# 8_-RK3399_SDRAM_Page.net
KiCad netlist of a schematic drawn in Altium Designer
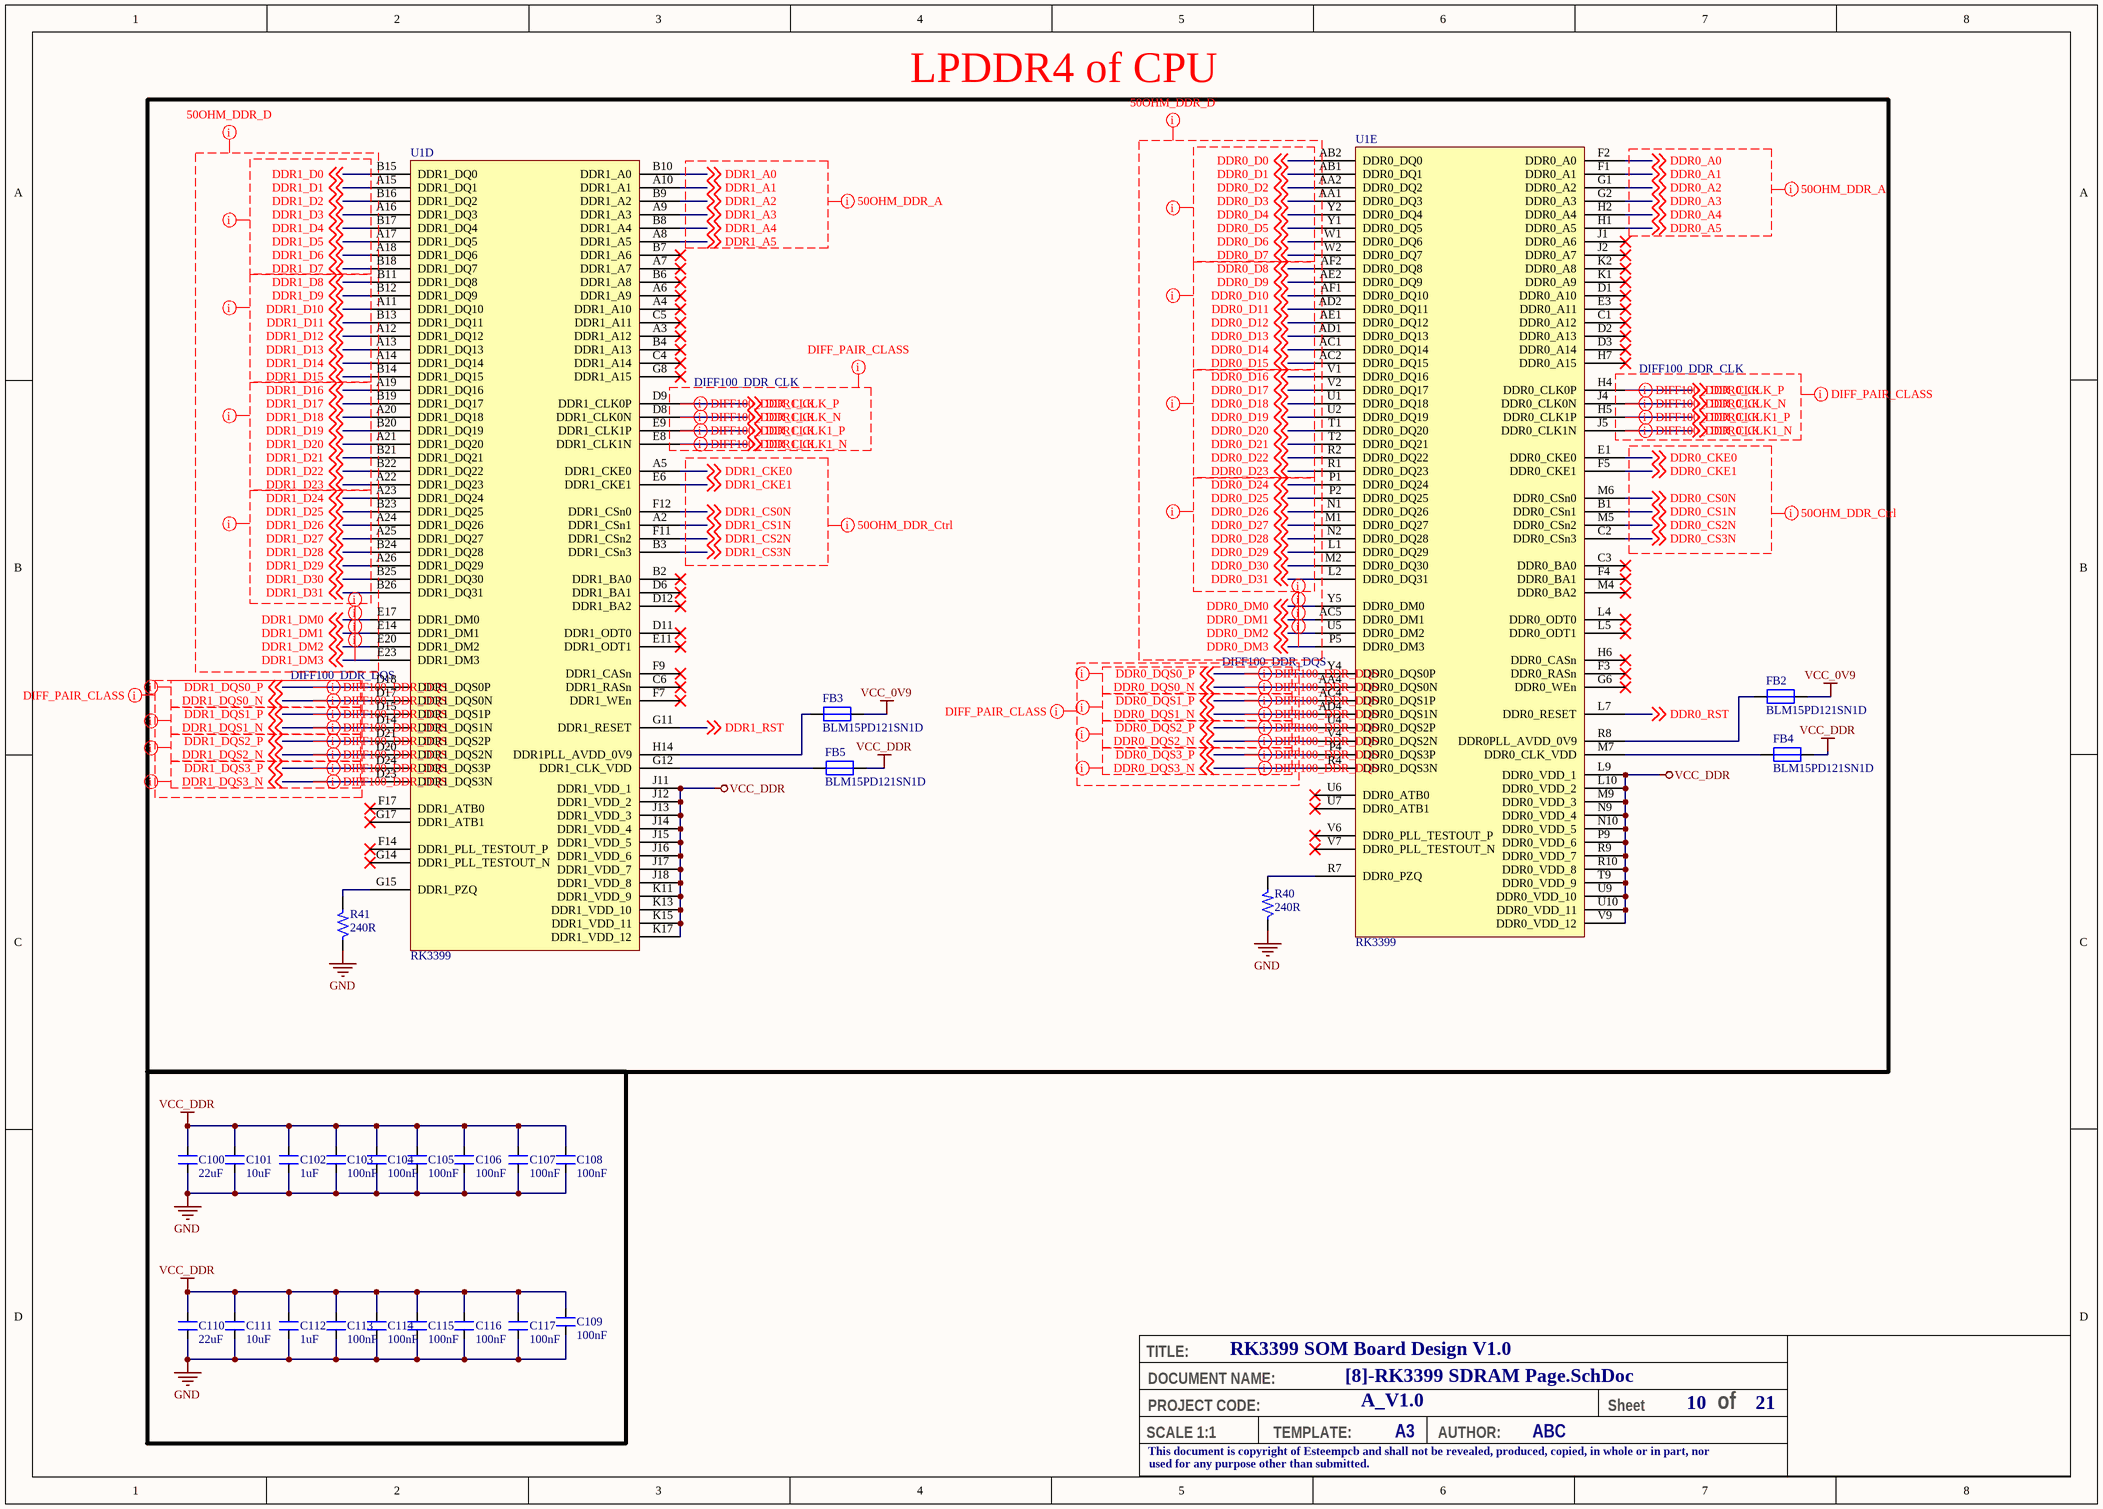
[diagram p0: [8]-RK3399 SDRAM Page.SchDoc]

(export (version "E")
  (design (tool "Eeschema 10.0.6"))
  (components
    (comp (ref "C100")
      (value "22uF")
      (footprint "CAP_0402")
      (description "22µF ±20% 6.3V Ceramic Capacitor X5R 0402 (1005 Metric)")
      (fields
        (field (name "MANUFACTURER") "Murata Electronics")
        (field (name "MANUFACTURER PART NUMBER") "CL05A226MQ5N6J8")
      )
      (libsource (lib "RK3399 _Module_Intlib") (part "CAP_22uF-6.3V-20%-0402"))
    )
    (comp (ref "C101")
      (value "10uF")
      (footprint "CAP_0402")
      (description "10µF ±20% 10V Ceramic Capacitor X5R 0402 (1005 Metric)")
      (fields
        (field (name "MANUFACTURER PART NUMBER") "CL05A106MP5NUNC")
        (field (name "MANUFACTURER") "Samsung Electro-Mechanics")
      )
      (libsource (lib "RK3399 _Module_Schlib") (part "CAP_10uF-10V-20%-0402"))
    )
    (comp (ref "C102")
      (value "1uF")
      (footprint "CAP_0201")
      (description "1µF ±20% 16V Ceramic Capacitor X5R 0201 (0603 Metric)")
      (fields
        (field (name "MANUFACTURER") "Samsung Electro-Mechanics")
        (field (name "MANUFACTURER PART NUMBER") "CL03A105MO3NRNH")
      )
      (libsource (lib "RK3399 _Module_Intlib") (part "CAP_1uF-16V-10%-0201"))
    )
    (comp (ref "C103")
      (value "100nF")
      (footprint "CAP_0201")
      (description "0.1µF ±10% 25V Ceramic Capacitor X5R 0201 (0603 Metric)")
      (fields
        (field (name "MANUFACTURER") "TDK Corporation")
        (field (name "MANUFACTURER PART NUMBER") "C0603X5R1E104K030BB")
      )
      (libsource (lib "RK3399 _Module_Intlib") (part "CAP_100nF-25V-10%-0201"))
    )
    (comp (ref "C104")
      (value "100nF")
      (footprint "CAP_0201")
      (description "0.1µF ±10% 25V Ceramic Capacitor X5R 0201 (0603 Metric)")
      (fields
        (field (name "MANUFACTURER") "TDK Corporation")
        (field (name "MANUFACTURER PART NUMBER") "C0603X5R1E104K030BB")
      )
      (libsource (lib "RK3399 _Module_Intlib") (part "CAP_100nF-25V-10%-0201"))
    )
    (comp (ref "C105")
      (value "100nF")
      (footprint "CAP_0201")
      (description "0.1µF ±10% 25V Ceramic Capacitor X5R 0201 (0603 Metric)")
      (fields
        (field (name "MANUFACTURER") "TDK Corporation")
        (field (name "MANUFACTURER PART NUMBER") "C0603X5R1E104K030BB")
      )
      (libsource (lib "RK3399 _Module_Intlib") (part "CAP_100nF-25V-10%-0201"))
    )
    (comp (ref "C106")
      (value "100nF")
      (footprint "CAP_0201")
      (description "0.1µF ±10% 25V Ceramic Capacitor X5R 0201 (0603 Metric)")
      (fields
        (field (name "MANUFACTURER") "TDK Corporation")
        (field (name "MANUFACTURER PART NUMBER") "C0603X5R1E104K030BB")
      )
      (libsource (lib "RK3399 _Module_Intlib") (part "CAP_100nF-25V-10%-0201"))
    )
    (comp (ref "C107")
      (value "100nF")
      (footprint "CAP_0201")
      (description "0.1µF ±10% 25V Ceramic Capacitor X5R 0201 (0603 Metric)")
      (fields
        (field (name "MANUFACTURER") "TDK Corporation")
        (field (name "MANUFACTURER PART NUMBER") "C0603X5R1E104K030BB")
      )
      (libsource (lib "RK3399 _Module_Intlib") (part "CAP_100nF-25V-10%-0201"))
    )
    (comp (ref "C108")
      (value "100nF")
      (footprint "CAP_0201")
      (description "0.1µF ±10% 25V Ceramic Capacitor X5R 0201 (0603 Metric)")
      (fields
        (field (name "MANUFACTURER") "TDK Corporation")
        (field (name "MANUFACTURER PART NUMBER") "C0603X5R1E104K030BB")
      )
      (libsource (lib "RK3399 _Module_Intlib") (part "CAP_100nF-25V-10%-0201"))
    )
    (comp (ref "C109")
      (value "100nF")
      (footprint "CAP_0201")
      (description "0.1µF ±10% 25V Ceramic Capacitor X5R 0201 (0603 Metric)")
      (fields
        (field (name "MANUFACTURER") "TDK Corporation")
        (field (name "MANUFACTURER PART NUMBER") "C0603X5R1E104K030BB")
      )
      (libsource (lib "RK3399 _Module_Intlib") (part "CAP_100nF-25V-10%-0201"))
    )
    (comp (ref "C110")
      (value "22uF")
      (footprint "CAP_0402")
      (description "22µF ±20% 6.3V Ceramic Capacitor X5R 0402 (1005 Metric)")
      (fields
        (field (name "MANUFACTURER") "Murata Electronics")
        (field (name "MANUFACTURER PART NUMBER") "CL05A226MQ5N6J8")
      )
      (libsource (lib "RK3399 _Module_Intlib") (part "CAP_22uF-6.3V-20%-0402"))
    )
    (comp (ref "C111")
      (value "10uF")
      (footprint "CAP_0402")
      (description "10µF ±20% 10V Ceramic Capacitor X5R 0402 (1005 Metric)")
      (fields
        (field (name "MANUFACTURER PART NUMBER") "CL05A106MP5NUNC")
        (field (name "MANUFACTURER") "Samsung Electro-Mechanics")
      )
      (libsource (lib "RK3399 _Module_Schlib") (part "CAP_10uF-10V-20%-0402"))
    )
    (comp (ref "C112")
      (value "1uF")
      (footprint "CAP_0201")
      (description "1µF ±20% 16V Ceramic Capacitor X5R 0201 (0603 Metric)")
      (fields
        (field (name "MANUFACTURER") "Samsung Electro-Mechanics")
        (field (name "MANUFACTURER PART NUMBER") "CL03A105MO3NRNH")
      )
      (libsource (lib "RK3399 _Module_Intlib") (part "CAP_1uF-16V-10%-0201"))
    )
    (comp (ref "C113")
      (value "100nF")
      (footprint "CAP_0201")
      (description "0.1µF ±10% 25V Ceramic Capacitor X5R 0201 (0603 Metric)")
      (fields
        (field (name "MANUFACTURER") "TDK Corporation")
        (field (name "MANUFACTURER PART NUMBER") "C0603X5R1E104K030BB")
      )
      (libsource (lib "RK3399 _Module_Intlib") (part "CAP_100nF-25V-10%-0201"))
    )
    (comp (ref "C114")
      (value "100nF")
      (footprint "CAP_0201")
      (description "0.1µF ±10% 25V Ceramic Capacitor X5R 0201 (0603 Metric)")
      (fields
        (field (name "MANUFACTURER") "TDK Corporation")
        (field (name "MANUFACTURER PART NUMBER") "C0603X5R1E104K030BB")
      )
      (libsource (lib "RK3399 _Module_Intlib") (part "CAP_100nF-25V-10%-0201"))
    )
    (comp (ref "C115")
      (value "100nF")
      (footprint "CAP_0201")
      (description "0.1µF ±10% 25V Ceramic Capacitor X5R 0201 (0603 Metric)")
      (fields
        (field (name "MANUFACTURER") "TDK Corporation")
        (field (name "MANUFACTURER PART NUMBER") "C0603X5R1E104K030BB")
      )
      (libsource (lib "RK3399 _Module_Intlib") (part "CAP_100nF-25V-10%-0201"))
    )
    (comp (ref "C116")
      (value "100nF")
      (footprint "CAP_0201")
      (description "0.1µF ±10% 25V Ceramic Capacitor X5R 0201 (0603 Metric)")
      (fields
        (field (name "MANUFACTURER") "TDK Corporation")
        (field (name "MANUFACTURER PART NUMBER") "C0603X5R1E104K030BB")
      )
      (libsource (lib "RK3399 _Module_Intlib") (part "CAP_100nF-25V-10%-0201"))
    )
    (comp (ref "C117")
      (value "100nF")
      (footprint "CAP_0201")
      (description "0.1µF ±10% 25V Ceramic Capacitor X5R 0201 (0603 Metric)")
      (fields
        (field (name "MANUFACTURER") "TDK Corporation")
        (field (name "MANUFACTURER PART NUMBER") "C0603X5R1E104K030BB")
      )
      (libsource (lib "RK3399 _Module_Intlib") (part "CAP_100nF-25V-10%-0201"))
    )
    (comp (ref "FB2")
      (value "BLM15PD121SN1D")
      (footprint "RES_0402")
      (description "120 Ohms @ 100MHz 1 Power Line Ferrite Bead 0402 (1005 Metric) 1.3A 90mOhm")
      (fields (field (name "MANUFACTURER") "Murata Electronics"))
      (libsource (lib "RK3399 _Module_Schlib") (part "FB_120R-1.3A-100Mhz-0402"))
    )
    (comp (ref "FB3")
      (value "BLM15PD121SN1D")
      (footprint "RES_0402")
      (description "120 Ohms @ 100MHz 1 Power Line Ferrite Bead 0402 (1005 Metric) 1.3A 90mOhm")
      (fields (field (name "MANUFACTURER") "Murata Electronics"))
      (libsource (lib "RK3399 _Module_Schlib") (part "FB_120R-1.3A-100Mhz-0402"))
    )
    (comp (ref "FB4")
      (value "BLM15PD121SN1D")
      (footprint "RES_0402")
      (description "120 Ohms @ 100MHz 1 Power Line Ferrite Bead 0402 (1005 Metric) 1.3A 90mOhm")
      (fields (field (name "MANUFACTURER") "Murata Electronics"))
      (libsource (lib "RK3399 _Module_Schlib") (part "FB_120R-1.3A-100Mhz-0402"))
    )
    (comp (ref "FB5")
      (value "BLM15PD121SN1D")
      (footprint "RES_0402")
      (description "120 Ohms @ 100MHz 1 Power Line Ferrite Bead 0402 (1005 Metric) 1.3A 90mOhm")
      (fields (field (name "MANUFACTURER") "Murata Electronics"))
      (libsource (lib "RK3399 _Module_Schlib") (part "FB_120R-1.3A-100Mhz-0402"))
    )
    (comp (ref "R40")
      (value "240R")
      (footprint "RES_0201")
      (description "240 Ohms ±1% 0.05W, 1/20W Chip Resistor 0201 (0603 Metric) Thick Film")
      (fields
        (field (name "MANUFACTURER") "Yageo")
        (field (name "MANUFACTURER PART NUMBER") "RC0201FR-07240RL")
      )
      (libsource (lib "RK3399 _Module_Intlib") (part "RES_240R-0.05W-1%-0201"))
    )
    (comp (ref "R41")
      (value "240R")
      (footprint "RES_0201")
      (description "240 Ohms ±1% 0.05W, 1/20W Chip Resistor 0201 (0603 Metric) Thick Film")
      (fields
        (field (name "MANUFACTURER") "Yageo")
        (field (name "MANUFACTURER PART NUMBER") "RC0201FR-07240RL")
      )
      (libsource (lib "RK3399 _Module_Intlib") (part "RES_240R-0.05W-1%-0201"))
    )
    (comp (ref "U1")
      (value "RK3399")
      (footprint "FBGA828_23_826X826")
      (description "RK3399 is a low power, high performance processor for computing, personal mobile.")
      (fields (field (name "MANUFACTURER") "Rockchip"))
      (libsource (lib "RK3399 _Module_Schlib") (part "IC_RK3399-FCBGA828"))
    )
  )
  (nets
    (net (code "1") (name "DDR0_A0") (class "Default")
      (node (ref "U1") (pin "F2") (pinfunction "DDR0_A0_F2") (pintype "passive"))
    )
    (net (code "2") (name "DDR0_A1") (class "Default")
      (node (ref "U1") (pin "F1") (pinfunction "DDR0_A1_F1") (pintype "passive"))
    )
    (net (code "3") (name "DDR0_A2") (class "Default")
      (node (ref "U1") (pin "G1") (pinfunction "DDR0_A2_G1") (pintype "passive"))
    )
    (net (code "4") (name "DDR0_A3") (class "Default")
      (node (ref "U1") (pin "G2") (pinfunction "DDR0_A3_G2") (pintype "passive"))
    )
    (net (code "5") (name "DDR0_A4") (class "Default")
      (node (ref "U1") (pin "H2") (pinfunction "DDR0_A4_H2") (pintype "passive"))
    )
    (net (code "6") (name "DDR0_A5") (class "Default")
      (node (ref "U1") (pin "H1") (pinfunction "DDR0_A5_H1") (pintype "passive"))
    )
    (net (code "7") (name "DDR0_CKE0") (class "Default")
      (node (ref "U1") (pin "E1") (pinfunction "DDR0_CKE0_E1") (pintype "passive"))
    )
    (net (code "8") (name "DDR0_CKE1") (class "Default")
      (node (ref "U1") (pin "F5") (pinfunction "DDR0_CKE1_F5") (pintype "passive"))
    )
    (net (code "9") (name "DDR0_CLK1_N") (class "Default")
      (node (ref "U1") (pin "J5") (pinfunction "DDR0_CLK1N_J5") (pintype "passive"))
    )
    (net (code "10") (name "DDR0_CLK1_P") (class "Default")
      (node (ref "U1") (pin "H5") (pinfunction "DDR0_CLK1P_H5") (pintype "passive"))
    )
    (net (code "11") (name "DDR0_CLK_N") (class "Default")
      (node (ref "U1") (pin "J4") (pinfunction "DDR0_CLK0N_J4") (pintype "passive"))
    )
    (net (code "12") (name "DDR0_CLK_P") (class "Default")
      (node (ref "U1") (pin "H4") (pinfunction "DDR0_CLK0P_H4") (pintype "passive"))
    )
    (net (code "13") (name "DDR0_CS0N") (class "Default")
      (node (ref "U1") (pin "M6") (pinfunction "DDR0_CSn0_M6") (pintype "passive"))
    )
    (net (code "14") (name "DDR0_CS1N") (class "Default")
      (node (ref "U1") (pin "B1") (pinfunction "DDR0_CSn1_B1") (pintype "passive"))
    )
    (net (code "15") (name "DDR0_CS2N") (class "Default")
      (node (ref "U1") (pin "M5") (pinfunction "DDR0_CSn2_M5") (pintype "passive"))
    )
    (net (code "16") (name "DDR0_CS3N") (class "Default")
      (node (ref "U1") (pin "C2") (pinfunction "DDR0_CSn3_C2") (pintype "passive"))
    )
    (net (code "17") (name "DDR0_D0") (class "Default")
      (node (ref "U1") (pin "AB2") (pinfunction "DDR0_DQ0_AB2") (pintype "passive"))
    )
    (net (code "18") (name "DDR0_D1") (class "Default")
      (node (ref "U1") (pin "AB1") (pinfunction "DDR0_DQ1_AB1") (pintype "passive"))
    )
    (net (code "19") (name "DDR0_D2") (class "Default")
      (node (ref "U1") (pin "AA2") (pinfunction "DDR0_DQ2_AA2") (pintype "passive"))
    )
    (net (code "20") (name "DDR0_D3") (class "Default")
      (node (ref "U1") (pin "AA1") (pinfunction "DDR0_DQ3_AA1") (pintype "passive"))
    )
    (net (code "21") (name "DDR0_D4") (class "Default")
      (node (ref "U1") (pin "Y2") (pinfunction "DDR0_DQ4_Y2") (pintype "passive"))
    )
    (net (code "22") (name "DDR0_D5") (class "Default")
      (node (ref "U1") (pin "Y1") (pinfunction "DDR0_DQ5_Y1") (pintype "passive"))
    )
    (net (code "23") (name "DDR0_D6") (class "Default")
      (node (ref "U1") (pin "W1") (pinfunction "DDR0_DQ6_W1") (pintype "passive"))
    )
    (net (code "24") (name "DDR0_D7") (class "Default")
      (node (ref "U1") (pin "W2") (pinfunction "DDR0_DQ7_W2") (pintype "passive"))
    )
    (net (code "25") (name "DDR0_D8") (class "Default")
      (node (ref "U1") (pin "AF2") (pinfunction "DDR0_DQ8_AF2") (pintype "passive"))
    )
    (net (code "26") (name "DDR0_D9") (class "Default")
      (node (ref "U1") (pin "AE2") (pinfunction "DDR0_DQ9_AE2") (pintype "passive"))
    )
    (net (code "27") (name "DDR0_D10") (class "Default")
      (node (ref "U1") (pin "AF1") (pinfunction "DDR0_DQ10_AF1") (pintype "passive"))
    )
    (net (code "28") (name "DDR0_D11") (class "Default")
      (node (ref "U1") (pin "AD2") (pinfunction "DDR0_DQ11_AD2") (pintype "passive"))
    )
    (net (code "29") (name "DDR0_D12") (class "Default")
      (node (ref "U1") (pin "AE1") (pinfunction "DDR0_DQ12_AE1") (pintype "passive"))
    )
    (net (code "30") (name "DDR0_D13") (class "Default")
      (node (ref "U1") (pin "AD1") (pinfunction "DDR0_DQ13_AD1") (pintype "passive"))
    )
    (net (code "31") (name "DDR0_D14") (class "Default")
      (node (ref "U1") (pin "AC1") (pinfunction "DDR0_DQ14_AC1") (pintype "passive"))
    )
    (net (code "32") (name "DDR0_D15") (class "Default")
      (node (ref "U1") (pin "AC2") (pinfunction "DDR0_DQ15_AC2") (pintype "passive"))
    )
    (net (code "33") (name "DDR0_D16") (class "Default")
      (node (ref "U1") (pin "V1") (pinfunction "DDR0_DQ16_V1") (pintype "passive"))
    )
    (net (code "34") (name "DDR0_D17") (class "Default")
      (node (ref "U1") (pin "V2") (pinfunction "DDR0_DQ17_V2") (pintype "passive"))
    )
    (net (code "35") (name "DDR0_D18") (class "Default")
      (node (ref "U1") (pin "U1") (pinfunction "DDR0_DQ18_U1") (pintype "passive"))
    )
    (net (code "36") (name "DDR0_D19") (class "Default")
      (node (ref "U1") (pin "U2") (pinfunction "DDR0_DQ19_U2") (pintype "passive"))
    )
    (net (code "37") (name "DDR0_D20") (class "Default")
      (node (ref "U1") (pin "T1") (pinfunction "DDR0_DQ20_T1") (pintype "passive"))
    )
    (net (code "38") (name "DDR0_D21") (class "Default")
      (node (ref "U1") (pin "T2") (pinfunction "DDR0_DQ21_T2") (pintype "passive"))
    )
    (net (code "39") (name "DDR0_D22") (class "Default")
      (node (ref "U1") (pin "R2") (pinfunction "DDR0_DQ22_R2") (pintype "passive"))
    )
    (net (code "40") (name "DDR0_D23") (class "Default")
      (node (ref "U1") (pin "R1") (pinfunction "DDR0_DQ23_R1") (pintype "passive"))
    )
    (net (code "41") (name "DDR0_D24") (class "Default")
      (node (ref "U1") (pin "P1") (pinfunction "DDR0_DQ24_P1") (pintype "passive"))
    )
    (net (code "42") (name "DDR0_D25") (class "Default")
      (node (ref "U1") (pin "P2") (pinfunction "DDR0_DQ25_P2") (pintype "passive"))
    )
    (net (code "43") (name "DDR0_D26") (class "Default")
      (node (ref "U1") (pin "N1") (pinfunction "DDR0_DQ26_N1") (pintype "passive"))
    )
    (net (code "44") (name "DDR0_D27") (class "Default")
      (node (ref "U1") (pin "M1") (pinfunction "DDR0_DQ27_M1") (pintype "passive"))
    )
    (net (code "45") (name "DDR0_D28") (class "Default")
      (node (ref "U1") (pin "N2") (pinfunction "DDR0_DQ28_N2") (pintype "passive"))
    )
    (net (code "46") (name "DDR0_D29") (class "Default")
      (node (ref "U1") (pin "L1") (pinfunction "DDR0_DQ29_L1") (pintype "passive"))
    )
    (net (code "47") (name "DDR0_D30") (class "Default")
      (node (ref "U1") (pin "M2") (pinfunction "DDR0_DQ30_M2") (pintype "passive"))
    )
    (net (code "48") (name "DDR0_D31") (class "Default")
      (node (ref "U1") (pin "L2") (pinfunction "DDR0_DQ31_L2") (pintype "passive"))
    )
    (net (code "49") (name "DDR0_DM0") (class "Default")
      (node (ref "U1") (pin "Y5") (pinfunction "DDR0_DM0_Y5") (pintype "passive"))
    )
    (net (code "50") (name "DDR0_DM1") (class "Default")
      (node (ref "U1") (pin "AC5") (pinfunction "DDR0_DM1_AC5") (pintype "passive"))
    )
    (net (code "51") (name "DDR0_DM2") (class "Default")
      (node (ref "U1") (pin "U5") (pinfunction "DDR0_DM2_U5") (pintype "passive"))
    )
    (net (code "52") (name "DDR0_DM3") (class "Default")
      (node (ref "U1") (pin "P5") (pinfunction "DDR0_DM3_P5") (pintype "passive"))
    )
    (net (code "53") (name "DDR0_DQS0_N") (class "Default")
      (node (ref "U1") (pin "AA4") (pinfunction "DDR0_DQS0N_AA4") (pintype "passive"))
    )
    (net (code "54") (name "DDR0_DQS0_P") (class "Default")
      (node (ref "U1") (pin "Y4") (pinfunction "DDR0_DQS0P_Y4") (pintype "passive"))
    )
    (net (code "55") (name "DDR0_DQS1_N") (class "Default")
      (node (ref "U1") (pin "AD4") (pinfunction "DDR0_DQS1N_AD4") (pintype "passive"))
    )
    (net (code "56") (name "DDR0_DQS1_P") (class "Default")
      (node (ref "U1") (pin "AC4") (pinfunction "DDR0_DQS1P_AC4") (pintype "passive"))
    )
    (net (code "57") (name "DDR0_DQS2_N") (class "Default")
      (node (ref "U1") (pin "V4") (pinfunction "DDR0_DQS2N_V4") (pintype "passive"))
    )
    (net (code "58") (name "DDR0_DQS2_P") (class "Default")
      (node (ref "U1") (pin "U4") (pinfunction "DDR0_DQS2P_U4") (pintype "passive"))
    )
    (net (code "59") (name "DDR0_DQS3_N") (class "Default")
      (node (ref "U1") (pin "R4") (pinfunction "DDR0_DQS3N_R4") (pintype "passive"))
    )
    (net (code "60") (name "DDR0_DQS3_P") (class "Default")
      (node (ref "U1") (pin "P4") (pinfunction "DDR0_DQS3P_P4") (pintype "passive"))
    )
    (net (code "61") (name "DDR0_RST") (class "Default")
      (node (ref "U1") (pin "L7") (pinfunction "DDR0_RESET_L7") (pintype "passive"))
    )
    (net (code "62") (name "DDR1_A0") (class "Default")
      (node (ref "U1") (pin "B10") (pinfunction "DDR1_A0_B10") (pintype "passive"))
    )
    (net (code "63") (name "DDR1_A1") (class "Default")
      (node (ref "U1") (pin "A10") (pinfunction "DDR1_A1_A10") (pintype "passive"))
    )
    (net (code "64") (name "DDR1_A2") (class "Default")
      (node (ref "U1") (pin "B9") (pinfunction "DDR1_A2_B9") (pintype "passive"))
    )
    (net (code "65") (name "DDR1_A3") (class "Default")
      (node (ref "U1") (pin "A9") (pinfunction "DDR1_A3_A9") (pintype "passive"))
    )
    (net (code "66") (name "DDR1_A4") (class "Default")
      (node (ref "U1") (pin "B8") (pinfunction "DDR1_A4_B8") (pintype "passive"))
    )
    (net (code "67") (name "DDR1_A5") (class "Default")
      (node (ref "U1") (pin "A8") (pinfunction "DDR1_A5_A8") (pintype "passive"))
    )
    (net (code "68") (name "DDR1_CKE0") (class "Default")
      (node (ref "U1") (pin "A5") (pinfunction "DDR1_CKE0_A5") (pintype "passive"))
    )
    (net (code "69") (name "DDR1_CKE1") (class "Default")
      (node (ref "U1") (pin "E6") (pinfunction "DDR1_CKE1_E6") (pintype "passive"))
    )
    (net (code "70") (name "DDR1_CLK1_N") (class "Default")
      (node (ref "U1") (pin "E8") (pinfunction "DDR1_CLK1N_E8") (pintype "passive"))
    )
    (net (code "71") (name "DDR1_CLK1_P") (class "Default")
      (node (ref "U1") (pin "E9") (pinfunction "DDR1_CLK1P_E9") (pintype "passive"))
    )
    (net (code "72") (name "DDR1_CLK_N") (class "Default")
      (node (ref "U1") (pin "D8") (pinfunction "DDR1_CLK0N_D8") (pintype "passive"))
    )
    (net (code "73") (name "DDR1_CLK_P") (class "Default")
      (node (ref "U1") (pin "D9") (pinfunction "DDR1_CLK0P_D9") (pintype "passive"))
    )
    (net (code "74") (name "DDR1_CS0N") (class "Default")
      (node (ref "U1") (pin "F12") (pinfunction "DDR1_CSn0_F12") (pintype "passive"))
    )
    (net (code "75") (name "DDR1_CS1N") (class "Default")
      (node (ref "U1") (pin "A2") (pinfunction "DDR1_CSn1_A2") (pintype "passive"))
    )
    (net (code "76") (name "DDR1_CS2N") (class "Default")
      (node (ref "U1") (pin "F11") (pinfunction "DDR1_CSn2_F11") (pintype "passive"))
    )
    (net (code "77") (name "DDR1_CS3N") (class "Default")
      (node (ref "U1") (pin "B3") (pinfunction "DDR1_CSn3_B3") (pintype "passive"))
    )
    (net (code "78") (name "DDR1_D0") (class "Default")
      (node (ref "U1") (pin "B15") (pinfunction "DDR1_DQ0_B15") (pintype "passive"))
    )
    (net (code "79") (name "DDR1_D1") (class "Default")
      (node (ref "U1") (pin "A15") (pinfunction "DDR1_DQ1_A15") (pintype "passive"))
    )
    (net (code "80") (name "DDR1_D2") (class "Default")
      (node (ref "U1") (pin "B16") (pinfunction "DDR1_DQ2_B16") (pintype "passive"))
    )
    (net (code "81") (name "DDR1_D3") (class "Default")
      (node (ref "U1") (pin "A16") (pinfunction "DDR1_DQ3_A16") (pintype "passive"))
    )
    (net (code "82") (name "DDR1_D4") (class "Default")
      (node (ref "U1") (pin "B17") (pinfunction "DDR1_DQ4_B17") (pintype "passive"))
    )
    (net (code "83") (name "DDR1_D5") (class "Default")
      (node (ref "U1") (pin "A17") (pinfunction "DDR1_DQ5_A17") (pintype "passive"))
    )
    (net (code "84") (name "DDR1_D6") (class "Default")
      (node (ref "U1") (pin "A18") (pinfunction "DDR1_DQ6_A18") (pintype "passive"))
    )
    (net (code "85") (name "DDR1_D7") (class "Default")
      (node (ref "U1") (pin "B18") (pinfunction "DDR1_DQ7_B18") (pintype "passive"))
    )
    (net (code "86") (name "DDR1_D8") (class "Default")
      (node (ref "U1") (pin "B11") (pinfunction "DDR1_DQ8_B11") (pintype "passive"))
    )
    (net (code "87") (name "DDR1_D9") (class "Default")
      (node (ref "U1") (pin "B12") (pinfunction "DDR1_DQ9_B12") (pintype "passive"))
    )
    (net (code "88") (name "DDR1_D10") (class "Default")
      (node (ref "U1") (pin "A11") (pinfunction "DDR1_DQ10_A11") (pintype "passive"))
    )
    (net (code "89") (name "DDR1_D11") (class "Default")
      (node (ref "U1") (pin "B13") (pinfunction "DDR1_DQ11_B13") (pintype "passive"))
    )
    (net (code "90") (name "DDR1_D12") (class "Default")
      (node (ref "U1") (pin "A12") (pinfunction "DDR1_DQ12_A12") (pintype "passive"))
    )
    (net (code "91") (name "DDR1_D13") (class "Default")
      (node (ref "U1") (pin "A13") (pinfunction "DDR1_DQ13_A13") (pintype "passive"))
    )
    (net (code "92") (name "DDR1_D14") (class "Default")
      (node (ref "U1") (pin "A14") (pinfunction "DDR1_DQ14_A14") (pintype "passive"))
    )
    (net (code "93") (name "DDR1_D15") (class "Default")
      (node (ref "U1") (pin "B14") (pinfunction "DDR1_DQ15_B14") (pintype "passive"))
    )
    (net (code "94") (name "DDR1_D16") (class "Default")
      (node (ref "U1") (pin "A19") (pinfunction "DDR1_DQ16_A19") (pintype "passive"))
    )
    (net (code "95") (name "DDR1_D17") (class "Default")
      (node (ref "U1") (pin "B19") (pinfunction "DDR1_DQ17_B19") (pintype "passive"))
    )
    (net (code "96") (name "DDR1_D18") (class "Default")
      (node (ref "U1") (pin "A20") (pinfunction "DDR1_DQ18_A20") (pintype "passive"))
    )
    (net (code "97") (name "DDR1_D19") (class "Default")
      (node (ref "U1") (pin "B20") (pinfunction "DDR1_DQ19_B20") (pintype "passive"))
    )
    (net (code "98") (name "DDR1_D20") (class "Default")
      (node (ref "U1") (pin "A21") (pinfunction "DDR1_DQ20_A21") (pintype "passive"))
    )
    (net (code "99") (name "DDR1_D21") (class "Default")
      (node (ref "U1") (pin "B21") (pinfunction "DDR1_DQ21_B21") (pintype "passive"))
    )
    (net (code "100") (name "DDR1_D22") (class "Default")
      (node (ref "U1") (pin "B22") (pinfunction "DDR1_DQ22_B22") (pintype "passive"))
    )
    (net (code "101") (name "DDR1_D23") (class "Default")
      (node (ref "U1") (pin "A22") (pinfunction "DDR1_DQ23_A22") (pintype "passive"))
    )
    (net (code "102") (name "DDR1_D24") (class "Default")
      (node (ref "U1") (pin "A23") (pinfunction "DDR1_DQ24_A23") (pintype "passive"))
    )
    (net (code "103") (name "DDR1_D25") (class "Default")
      (node (ref "U1") (pin "B23") (pinfunction "DDR1_DQ25_B23") (pintype "passive"))
    )
    (net (code "104") (name "DDR1_D26") (class "Default")
      (node (ref "U1") (pin "A24") (pinfunction "DDR1_DQ26_A24") (pintype "passive"))
    )
    (net (code "105") (name "DDR1_D27") (class "Default")
      (node (ref "U1") (pin "A25") (pinfunction "DDR1_DQ27_A25") (pintype "passive"))
    )
    (net (code "106") (name "DDR1_D28") (class "Default")
      (node (ref "U1") (pin "B24") (pinfunction "DDR1_DQ28_B24") (pintype "passive"))
    )
    (net (code "107") (name "DDR1_D29") (class "Default")
      (node (ref "U1") (pin "A26") (pinfunction "DDR1_DQ29_A26") (pintype "passive"))
    )
    (net (code "108") (name "DDR1_D30") (class "Default")
      (node (ref "U1") (pin "B25") (pinfunction "DDR1_DQ30_B25") (pintype "passive"))
    )
    (net (code "109") (name "DDR1_D31") (class "Default")
      (node (ref "U1") (pin "B26") (pinfunction "DDR1_DQ31_B26") (pintype "passive"))
    )
    (net (code "110") (name "DDR1_DM0") (class "Default")
      (node (ref "U1") (pin "E17") (pinfunction "DDR1_DM0_E17") (pintype "passive"))
    )
    (net (code "111") (name "DDR1_DM1") (class "Default")
      (node (ref "U1") (pin "E14") (pinfunction "DDR1_DM1_E14") (pintype "passive"))
    )
    (net (code "112") (name "DDR1_DM2") (class "Default")
      (node (ref "U1") (pin "E20") (pinfunction "DDR1_DM2_E20") (pintype "passive"))
    )
    (net (code "113") (name "DDR1_DM3") (class "Default")
      (node (ref "U1") (pin "E23") (pinfunction "DDR1_DM3_E23") (pintype "passive"))
    )
    (net (code "114") (name "DDR1_DQS0_N") (class "Default")
      (node (ref "U1") (pin "D17") (pinfunction "DDR1_DQS0N_D17") (pintype "passive"))
    )
    (net (code "115") (name "DDR1_DQS0_P") (class "Default")
      (node (ref "U1") (pin "D18") (pinfunction "DDR1_DQS0P_D18") (pintype "passive"))
    )
    (net (code "116") (name "DDR1_DQS1_N") (class "Default")
      (node (ref "U1") (pin "D14") (pinfunction "DDR1_DQS1N_D14") (pintype "passive"))
    )
    (net (code "117") (name "DDR1_DQS1_P") (class "Default")
      (node (ref "U1") (pin "D15") (pinfunction "DDR1_DQS1P_D15") (pintype "passive"))
    )
    (net (code "118") (name "DDR1_DQS2_N") (class "Default")
      (node (ref "U1") (pin "D20") (pinfunction "DDR1_DQS2N_D20") (pintype "passive"))
    )
    (net (code "119") (name "DDR1_DQS2_P") (class "Default")
      (node (ref "U1") (pin "D21") (pinfunction "DDR1_DQS2P_D21") (pintype "passive"))
    )
    (net (code "120") (name "DDR1_DQS3_N") (class "Default")
      (node (ref "U1") (pin "D23") (pinfunction "DDR1_DQS3N_D23") (pintype "passive"))
    )
    (net (code "121") (name "DDR1_DQS3_P") (class "Default")
      (node (ref "U1") (pin "D24") (pinfunction "DDR1_DQS3P_D24") (pintype "passive"))
    )
    (net (code "122") (name "DDR1_RST") (class "Default")
      (node (ref "U1") (pin "G11") (pinfunction "DDR1_RESET_G11") (pintype "passive"))
    )
    (net (code "123") (name "GND") (class "Default")
      (node (ref "C100") (pin "1") (pinfunction "1_1") (pintype "passive"))
      (node (ref "C101") (pin "1") (pinfunction "1_1") (pintype "passive"))
      (node (ref "C102") (pin "1") (pinfunction "1_1") (pintype "passive"))
      (node (ref "C103") (pin "1") (pinfunction "1_1") (pintype "passive"))
      (node (ref "C104") (pin "1") (pinfunction "1_1") (pintype "passive"))
      (node (ref "C105") (pin "1") (pinfunction "1_1") (pintype "passive"))
      (node (ref "C106") (pin "1") (pinfunction "1_1") (pintype "passive"))
      (node (ref "C107") (pin "1") (pinfunction "1_1") (pintype "passive"))
      (node (ref "C108") (pin "1") (pinfunction "1_1") (pintype "passive"))
      (node (ref "C109") (pin "1") (pinfunction "1_1") (pintype "passive"))
      (node (ref "C110") (pin "1") (pinfunction "1_1") (pintype "passive"))
      (node (ref "C111") (pin "1") (pinfunction "1_1") (pintype "passive"))
      (node (ref "C112") (pin "1") (pinfunction "1_1") (pintype "passive"))
      (node (ref "C113") (pin "1") (pinfunction "1_1") (pintype "passive"))
      (node (ref "C114") (pin "1") (pinfunction "1_1") (pintype "passive"))
      (node (ref "C115") (pin "1") (pinfunction "1_1") (pintype "passive"))
      (node (ref "C116") (pin "1") (pinfunction "1_1") (pintype "passive"))
      (node (ref "C117") (pin "1") (pinfunction "1_1") (pintype "passive"))
      (node (ref "R40") (pin "1") (pinfunction "1_1") (pintype "passive"))
      (node (ref "R41") (pin "1") (pinfunction "1_1") (pintype "passive"))
    )
    (net (code "124") (name "Net-(U1D-DDR1PLL_AVDD_0V9)") (class "Default")
      (node (ref "FB3") (pin "1") (pinfunction "1_1") (pintype "passive"))
      (node (ref "U1") (pin "H14") (pinfunction "DDR1PLL_AVDD_0V9_H14") (pintype "passive"))
    )
    (net (code "125") (name "Net-(U1D-DDR1_CLK_VDD)") (class "Default")
      (node (ref "FB5") (pin "1") (pinfunction "1_1") (pintype "passive"))
      (node (ref "U1") (pin "G12") (pinfunction "DDR1_CLK_VDD_G12") (pintype "passive"))
    )
    (net (code "126") (name "Net-(U1D-DDR1_PZQ)") (class "Default")
      (node (ref "R41") (pin "2") (pinfunction "2_2") (pintype "passive"))
      (node (ref "U1") (pin "G15") (pinfunction "DDR1_PZQ_G15") (pintype "passive"))
    )
    (net (code "127") (name "Net-(U1E-DDR0PLL_AVDD_0V9)") (class "Default")
      (node (ref "FB2") (pin "1") (pinfunction "1_1") (pintype "passive"))
      (node (ref "U1") (pin "R8") (pinfunction "DDR0PLL_AVDD_0V9_R8") (pintype "passive"))
    )
    (net (code "128") (name "Net-(U1E-DDR0_CLK_VDD)") (class "Default")
      (node (ref "FB4") (pin "1") (pinfunction "1_1") (pintype "passive"))
      (node (ref "U1") (pin "M7") (pinfunction "DDR0_CLK_VDD_M7") (pintype "passive"))
    )
    (net (code "129") (name "Net-(U1E-DDR0_PZQ)") (class "Default")
      (node (ref "R40") (pin "2") (pinfunction "2_2") (pintype "passive"))
      (node (ref "U1") (pin "R7") (pinfunction "DDR0_PZQ_R7") (pintype "passive"))
    )
    (net (code "130") (name "VCC_0V9") (class "Default")
      (node (ref "FB2") (pin "2") (pinfunction "2_2") (pintype "passive"))
      (node (ref "FB3") (pin "2") (pinfunction "2_2") (pintype "passive"))
    )
    (net (code "131") (name "VCC_DDR") (class "Default")
      (node (ref "C100") (pin "2") (pinfunction "2_2") (pintype "passive"))
      (node (ref "C101") (pin "2") (pinfunction "2_2") (pintype "passive"))
      (node (ref "C102") (pin "2") (pinfunction "2_2") (pintype "passive"))
      (node (ref "C103") (pin "2") (pinfunction "2_2") (pintype "passive"))
      (node (ref "C104") (pin "2") (pinfunction "2_2") (pintype "passive"))
      (node (ref "C105") (pin "2") (pinfunction "2_2") (pintype "passive"))
      (node (ref "C106") (pin "2") (pinfunction "2_2") (pintype "passive"))
      (node (ref "C107") (pin "2") (pinfunction "2_2") (pintype "passive"))
      (node (ref "C108") (pin "2") (pinfunction "2_2") (pintype "passive"))
      (node (ref "C109") (pin "2") (pinfunction "2_2") (pintype "passive"))
      (node (ref "C110") (pin "2") (pinfunction "2_2") (pintype "passive"))
      (node (ref "C111") (pin "2") (pinfunction "2_2") (pintype "passive"))
      (node (ref "C112") (pin "2") (pinfunction "2_2") (pintype "passive"))
      (node (ref "C113") (pin "2") (pinfunction "2_2") (pintype "passive"))
      (node (ref "C114") (pin "2") (pinfunction "2_2") (pintype "passive"))
      (node (ref "C115") (pin "2") (pinfunction "2_2") (pintype "passive"))
      (node (ref "C116") (pin "2") (pinfunction "2_2") (pintype "passive"))
      (node (ref "C117") (pin "2") (pinfunction "2_2") (pintype "passive"))
      (node (ref "FB4") (pin "2") (pinfunction "2_2") (pintype "passive"))
      (node (ref "FB5") (pin "2") (pinfunction "2_2") (pintype "passive"))
      (node (ref "U1") (pin "J11") (pinfunction "DDR1_VDD_1_J11") (pintype "passive"))
      (node (ref "U1") (pin "J12") (pinfunction "DDR1_VDD_2_J12") (pintype "passive"))
      (node (ref "U1") (pin "J13") (pinfunction "DDR1_VDD_3_J13") (pintype "passive"))
      (node (ref "U1") (pin "J14") (pinfunction "DDR1_VDD_4_J14") (pintype "passive"))
      (node (ref "U1") (pin "J15") (pinfunction "DDR1_VDD_5_J15") (pintype "passive"))
      (node (ref "U1") (pin "J16") (pinfunction "DDR1_VDD_6_J16") (pintype "passive"))
      (node (ref "U1") (pin "J17") (pinfunction "DDR1_VDD_7_J17") (pintype "passive"))
      (node (ref "U1") (pin "J18") (pinfunction "DDR1_VDD_8_J18") (pintype "passive"))
      (node (ref "U1") (pin "K11") (pinfunction "DDR1_VDD_9_K11") (pintype "passive"))
      (node (ref "U1") (pin "K13") (pinfunction "DDR1_VDD_10_K13") (pintype "passive"))
      (node (ref "U1") (pin "K15") (pinfunction "DDR1_VDD_11_K15") (pintype "passive"))
      (node (ref "U1") (pin "K17") (pinfunction "DDR1_VDD_12_K17") (pintype "passive"))
      (node (ref "U1") (pin "L10") (pinfunction "DDR0_VDD_2_L10") (pintype "passive"))
      (node (ref "U1") (pin "L9") (pinfunction "DDR0_VDD_1_L9") (pintype "passive"))
      (node (ref "U1") (pin "M9") (pinfunction "DDR0_VDD_3_M9") (pintype "passive"))
      (node (ref "U1") (pin "N10") (pinfunction "DDR0_VDD_5_N10") (pintype "passive"))
      (node (ref "U1") (pin "N9") (pinfunction "DDR0_VDD_4_N9") (pintype "passive"))
      (node (ref "U1") (pin "P9") (pinfunction "DDR0_VDD_6_P9") (pintype "passive"))
      (node (ref "U1") (pin "R10") (pinfunction "DDR0_VDD_8_R10") (pintype "passive"))
      (node (ref "U1") (pin "R9") (pinfunction "DDR0_VDD_7_R9") (pintype "passive"))
      (node (ref "U1") (pin "T9") (pinfunction "DDR0_VDD_9_T9") (pintype "passive"))
      (node (ref "U1") (pin "U10") (pinfunction "DDR0_VDD_11_U10") (pintype "passive"))
      (node (ref "U1") (pin "U9") (pinfunction "DDR0_VDD_10_U9") (pintype "passive"))
      (node (ref "U1") (pin "V9") (pinfunction "DDR0_VDD_12_V9") (pintype "passive"))
    )
    (net (code "132") (name "unconnected-(U1D-DDR1_A6-PadB7)") (class "Default")
      (node (ref "U1") (pin "B7") (pinfunction "DDR1_A6_B7") (pintype "passive+no_connect"))
    )
    (net (code "133") (name "unconnected-(U1D-DDR1_A7-PadA7)") (class "Default")
      (node (ref "U1") (pin "A7") (pinfunction "DDR1_A7_A7") (pintype "passive+no_connect"))
    )
    (net (code "134") (name "unconnected-(U1D-DDR1_A8-PadB6)") (class "Default")
      (node (ref "U1") (pin "B6") (pinfunction "DDR1_A8_B6") (pintype "passive+no_connect"))
    )
    (net (code "135") (name "unconnected-(U1D-DDR1_A9-PadA6)") (class "Default")
      (node (ref "U1") (pin "A6") (pinfunction "DDR1_A9_A6") (pintype "passive+no_connect"))
    )
    (net (code "136") (name "unconnected-(U1D-DDR1_A10-PadA4)") (class "Default")
      (node (ref "U1") (pin "A4") (pinfunction "DDR1_A10_A4") (pintype "passive+no_connect"))
    )
    (net (code "137") (name "unconnected-(U1D-DDR1_A11-PadC5)") (class "Default")
      (node (ref "U1") (pin "C5") (pinfunction "DDR1_A11_C5") (pintype "passive+no_connect"))
    )
    (net (code "138") (name "unconnected-(U1D-DDR1_A12-PadA3)") (class "Default")
      (node (ref "U1") (pin "A3") (pinfunction "DDR1_A12_A3") (pintype "passive+no_connect"))
    )
    (net (code "139") (name "unconnected-(U1D-DDR1_A13-PadB4)") (class "Default")
      (node (ref "U1") (pin "B4") (pinfunction "DDR1_A13_B4") (pintype "passive+no_connect"))
    )
    (net (code "140") (name "unconnected-(U1D-DDR1_A14-PadC4)") (class "Default")
      (node (ref "U1") (pin "C4") (pinfunction "DDR1_A14_C4") (pintype "passive+no_connect"))
    )
    (net (code "141") (name "unconnected-(U1D-DDR1_A15-PadG8)") (class "Default")
      (node (ref "U1") (pin "G8") (pinfunction "DDR1_A15_G8") (pintype "passive+no_connect"))
    )
    (net (code "142") (name "unconnected-(U1D-DDR1_ATB0-PadF17)") (class "Default")
      (node (ref "U1") (pin "F17") (pinfunction "DDR1_ATB0_F17") (pintype "passive+no_connect"))
    )
    (net (code "143") (name "unconnected-(U1D-DDR1_ATB1-PadG17)") (class "Default")
      (node (ref "U1") (pin "G17") (pinfunction "DDR1_ATB1_G17") (pintype "passive+no_connect"))
    )
    (net (code "144") (name "unconnected-(U1D-DDR1_BA0-PadB2)") (class "Default")
      (node (ref "U1") (pin "B2") (pinfunction "DDR1_BA0_B2") (pintype "passive+no_connect"))
    )
    (net (code "145") (name "unconnected-(U1D-DDR1_BA1-PadD6)") (class "Default")
      (node (ref "U1") (pin "D6") (pinfunction "DDR1_BA1_D6") (pintype "passive+no_connect"))
    )
    (net (code "146") (name "unconnected-(U1D-DDR1_BA2-PadD12)") (class "Default")
      (node (ref "U1") (pin "D12") (pinfunction "DDR1_BA2_D12") (pintype "passive+no_connect"))
    )
    (net (code "147") (name "unconnected-(U1D-DDR1_CASn-PadF9)") (class "Default")
      (node (ref "U1") (pin "F9") (pinfunction "DDR1_CASn_F9") (pintype "passive+no_connect"))
    )
    (net (code "148") (name "unconnected-(U1D-DDR1_ODT0-PadD11)") (class "Default")
      (node (ref "U1") (pin "D11") (pinfunction "DDR1_ODT0_D11") (pintype "passive+no_connect"))
    )
    (net (code "149") (name "unconnected-(U1D-DDR1_ODT1-PadE11)") (class "Default")
      (node (ref "U1") (pin "E11") (pinfunction "DDR1_ODT1_E11") (pintype "passive+no_connect"))
    )
    (net (code "150") (name "unconnected-(U1D-DDR1_PLL_TESTOUT_N-PadG14)") (class "Default")
      (node (ref "U1") (pin "G14") (pinfunction "DDR1_PLL_TESTOUT_N_G14") (pintype "passive+no_connect"))
    )
    (net (code "151") (name "unconnected-(U1D-DDR1_PLL_TESTOUT_P-PadF14)") (class "Default")
      (node (ref "U1") (pin "F14") (pinfunction "DDR1_PLL_TESTOUT_P_F14") (pintype "passive+no_connect"))
    )
    (net (code "152") (name "unconnected-(U1D-DDR1_RASn-PadC6)") (class "Default")
      (node (ref "U1") (pin "C6") (pinfunction "DDR1_RASn_C6") (pintype "passive+no_connect"))
    )
    (net (code "153") (name "unconnected-(U1D-DDR1_WEn-PadF7)") (class "Default")
      (node (ref "U1") (pin "F7") (pinfunction "DDR1_WEn_F7") (pintype "passive+no_connect"))
    )
    (net (code "154") (name "unconnected-(U1E-DDR0_A6-PadJ1)") (class "Default")
      (node (ref "U1") (pin "J1") (pinfunction "DDR0_A6_J1") (pintype "passive+no_connect"))
    )
    (net (code "155") (name "unconnected-(U1E-DDR0_A7-PadJ2)") (class "Default")
      (node (ref "U1") (pin "J2") (pinfunction "DDR0_A7_J2") (pintype "passive+no_connect"))
    )
    (net (code "156") (name "unconnected-(U1E-DDR0_A8-PadK2)") (class "Default")
      (node (ref "U1") (pin "K2") (pinfunction "DDR0_A8_K2") (pintype "passive+no_connect"))
    )
    (net (code "157") (name "unconnected-(U1E-DDR0_A9-PadK1)") (class "Default")
      (node (ref "U1") (pin "K1") (pinfunction "DDR0_A9_K1") (pintype "passive+no_connect"))
    )
    (net (code "158") (name "unconnected-(U1E-DDR0_A10-PadD1)") (class "Default")
      (node (ref "U1") (pin "D1") (pinfunction "DDR0_A10_D1") (pintype "passive+no_connect"))
    )
    (net (code "159") (name "unconnected-(U1E-DDR0_A11-PadE3)") (class "Default")
      (node (ref "U1") (pin "E3") (pinfunction "DDR0_A11_E3") (pintype "passive+no_connect"))
    )
    (net (code "160") (name "unconnected-(U1E-DDR0_A12-PadC1)") (class "Default")
      (node (ref "U1") (pin "C1") (pinfunction "DDR0_A12_C1") (pintype "passive+no_connect"))
    )
    (net (code "161") (name "unconnected-(U1E-DDR0_A13-PadD2)") (class "Default")
      (node (ref "U1") (pin "D2") (pinfunction "DDR0_A13_D2") (pintype "passive+no_connect"))
    )
    (net (code "162") (name "unconnected-(U1E-DDR0_A14-PadD3)") (class "Default")
      (node (ref "U1") (pin "D3") (pinfunction "DDR0_A14_D3") (pintype "passive+no_connect"))
    )
    (net (code "163") (name "unconnected-(U1E-DDR0_A15-PadH7)") (class "Default")
      (node (ref "U1") (pin "H7") (pinfunction "DDR0_A15_H7") (pintype "passive+no_connect"))
    )
    (net (code "164") (name "unconnected-(U1E-DDR0_ATB0-PadU6)") (class "Default")
      (node (ref "U1") (pin "U6") (pinfunction "DDR0_ATB0_U6") (pintype "passive+no_connect"))
    )
    (net (code "165") (name "unconnected-(U1E-DDR0_ATB1-PadU7)") (class "Default")
      (node (ref "U1") (pin "U7") (pinfunction "DDR0_ATB1_U7") (pintype "passive+no_connect"))
    )
    (net (code "166") (name "unconnected-(U1E-DDR0_BA0-PadC3)") (class "Default")
      (node (ref "U1") (pin "C3") (pinfunction "DDR0_BA0_C3") (pintype "passive+no_connect"))
    )
    (net (code "167") (name "unconnected-(U1E-DDR0_BA1-PadF4)") (class "Default")
      (node (ref "U1") (pin "F4") (pinfunction "DDR0_BA1_F4") (pintype "passive+no_connect"))
    )
    (net (code "168") (name "unconnected-(U1E-DDR0_BA2-PadM4)") (class "Default")
      (node (ref "U1") (pin "M4") (pinfunction "DDR0_BA2_M4") (pintype "passive+no_connect"))
    )
    (net (code "169") (name "unconnected-(U1E-DDR0_CASn-PadH6)") (class "Default")
      (node (ref "U1") (pin "H6") (pinfunction "DDR0_CASn_H6") (pintype "passive+no_connect"))
    )
    (net (code "170") (name "unconnected-(U1E-DDR0_ODT0-PadL4)") (class "Default")
      (node (ref "U1") (pin "L4") (pinfunction "DDR0_ODT0_L4") (pintype "passive+no_connect"))
    )
    (net (code "171") (name "unconnected-(U1E-DDR0_ODT1-PadL5)") (class "Default")
      (node (ref "U1") (pin "L5") (pinfunction "DDR0_ODT1_L5") (pintype "passive+no_connect"))
    )
    (net (code "172") (name "unconnected-(U1E-DDR0_PLL_TESTOUT_N-PadV7)") (class "Default")
      (node (ref "U1") (pin "V7") (pinfunction "DDR0_PLL_TESTOUT_N_V7") (pintype "passive+no_connect"))
    )
    (net (code "173") (name "unconnected-(U1E-DDR0_PLL_TESTOUT_P-PadV6)") (class "Default")
      (node (ref "U1") (pin "V6") (pinfunction "DDR0_PLL_TESTOUT_P_V6") (pintype "passive+no_connect"))
    )
    (net (code "174") (name "unconnected-(U1E-DDR0_RASn-PadF3)") (class "Default")
      (node (ref "U1") (pin "F3") (pinfunction "DDR0_RASn_F3") (pintype "passive+no_connect"))
    )
    (net (code "175") (name "unconnected-(U1E-DDR0_WEn-PadG6)") (class "Default")
      (node (ref "U1") (pin "G6") (pinfunction "DDR0_WEn_G6") (pintype "passive+no_connect"))
    )
  )
)
